# Top_level.net
KiCad netlist of a schematic drawn in Altium Designer
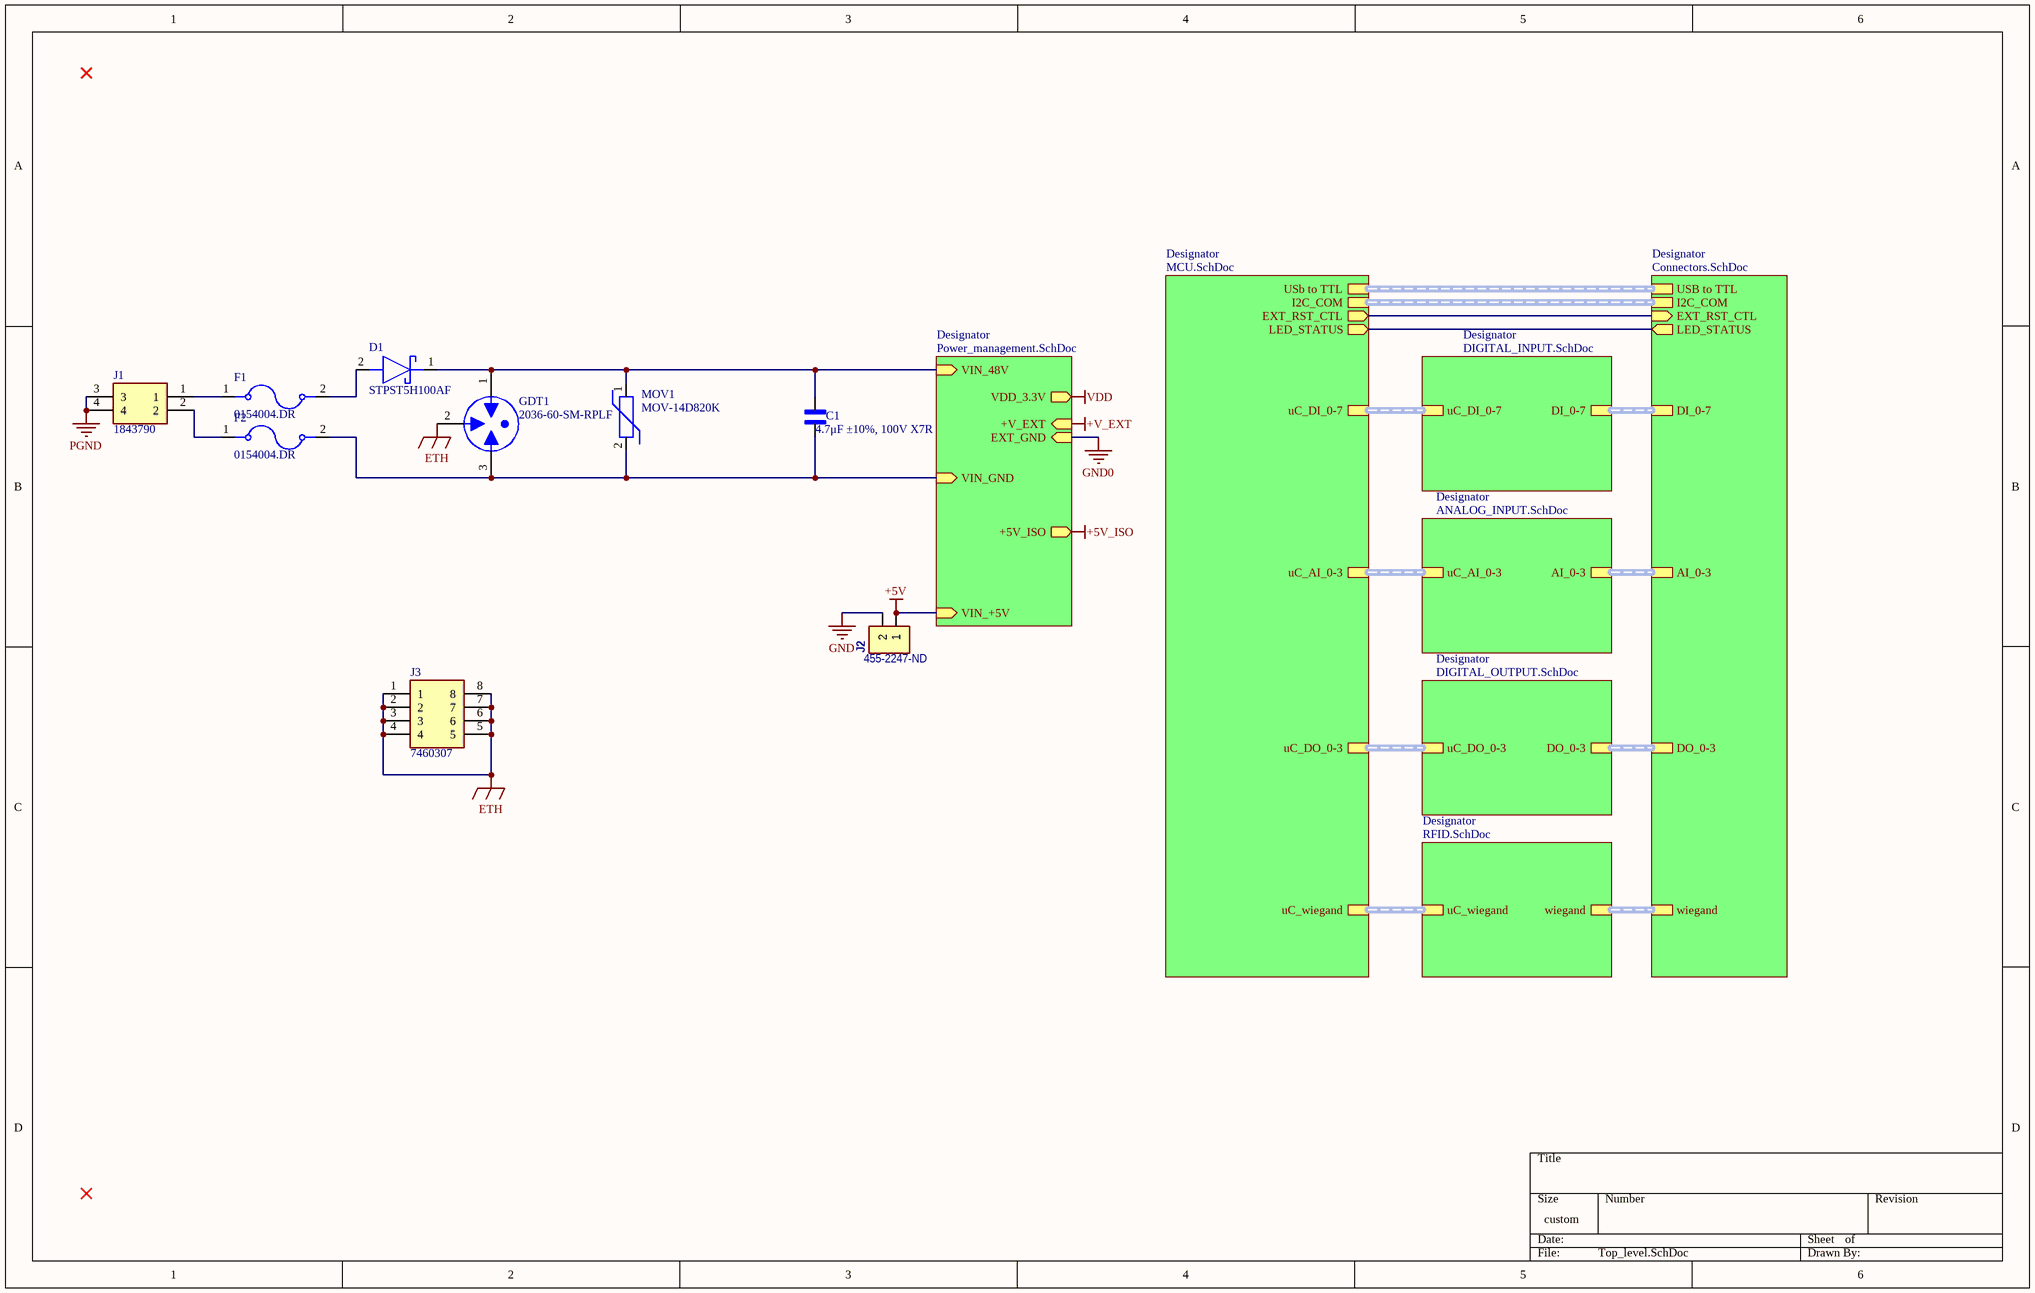
[diagram p0: Top_level.SchDoc]

(export (version "E")
  (design (tool "Eeschema 10.0.6"))
  (components
    (comp (ref "C1")
      (value "4.7μF ±10%, 100V X7R")
      (footprint "1210_C")
      (fields (field (name "MP") "LD03ZD475MAB2A"))
      (libsource (lib "DC_DC") (part "CAP"))
    )
    (comp (ref "D1")
      (value "STPST5H100AF")
      (footprint "SODFL4724X103N")
      (description "Schottky Diode")
      (fields (field (name "MOUSER PART NUMBER") "511-STPST5H100AF"))
      (libsource (lib "DC_DC") (part "STPST5H100AF"))
    )
    (comp (ref "F1")
      (value "0154004.DR")
      (footprint "FUSE_0154004.DR")
      (description "154/154T/154L/154TL Series OMNI-BLOKÂ® Fuse and Holder Assembly")
      (libsource (lib "DC_DC") (part "0154004.DR"))
    )
    (comp (ref "F2")
      (value "0154004.DR")
      (footprint "FUSE_0154004.DR")
      (description "154/154T/154L/154TL Series OMNI-BLOKÂ® Fuse and Holder Assembly")
      (libsource (lib "DC_DC") (part "0154004.DR"))
    )
    (comp (ref "GDT1")
      (value "2036-60-SM-RPLF")
      (footprint "2036-60-SM-RPLF")
      (description "Gas Discharge Tubes - GDTs / Gas Plasma Arrestors Sparkover100V/s 600V Miniature 3 Pole")
      (libsource (lib "DC_DC") (part "2036-60-SM-RPLF"))
    )
    (comp (ref "J1")
      (value "1843790")
      (footprint "SamacSys:1843790")
      (description "Connector")
      (fields (field (name "MOUSER PART NUMBER") "651-1843790"))
      (libsource (lib "*") (part "1843790"))
    )
    (comp (ref "J2")
      (value "455-2247-ND")
      (footprint "CON_HDR1x2")
      (libsource (lib "IIOT_GATEWAY_MT7621") (part "CON_HDR1x2"))
    )
    (comp (ref "J3")
      (value "7460307")
      (footprint "7460307")
      (description "Connector")
      (fields (field (name "MOUSER PART NUMBER") "710-7460307"))
      (libsource (lib "DC_DC") (part "7460307"))
    )
    (comp (ref "MOV1")
      (value "MOV-14D820K")
      (footprint "MOV-14D820K")
      (description "Varistors 82volts 14mm")
      (fields (field (name "MP") "MOV-14D471K") (field (name "MF") "Bourns"))
      (libsource (lib "DC_DC") (part "MOV-14D820K"))
    )
  )
  (nets
    (net (code "1") (name "+5V") (class "Default")
      (node (ref "J2") (pin "1") (pinfunction "1_1") (pintype "passive"))
    )
    (net (code "11") (name "/VIN_48V") (class "Default")
      (node (ref "C1") (pin "1") (pinfunction "1_1") (pintype "passive"))
      (node (ref "D1") (pin "1") (pinfunction "K_1") (pintype "passive"))
      (node (ref "GDT1") (pin "1") (pinfunction "A_1") (pintype "passive"))
      (node (ref "MOV1") (pin "1") (pinfunction "1_1") (pintype "bidirectional"))
    )
    (net (code "12") (name "/VIN_GND") (class "Default")
      (node (ref "C1") (pin "2") (pinfunction "2_2") (pintype "passive"))
      (node (ref "F2") (pin "2") (pinfunction "2_2") (pintype "passive"))
      (node (ref "GDT1") (pin "3") (pinfunction "B_3") (pintype "passive"))
      (node (ref "MOV1") (pin "2") (pinfunction "2_2") (pintype "bidirectional"))
    )
    (net (code "18") (name "ETH") (class "Default")
      (node (ref "GDT1") (pin "2") (pinfunction "E_2") (pintype "passive"))
      (node (ref "J3") (pin "1") (pinfunction "1_1") (pintype "passive"))
      (node (ref "J3") (pin "2") (pinfunction "2_2") (pintype "passive"))
      (node (ref "J3") (pin "3") (pinfunction "3_3") (pintype "passive"))
      (node (ref "J3") (pin "4") (pinfunction "4_4") (pintype "passive"))
      (node (ref "J3") (pin "5") (pinfunction "5_5") (pintype "passive"))
      (node (ref "J3") (pin "6") (pinfunction "6_6") (pintype "passive"))
      (node (ref "J3") (pin "7") (pinfunction "7_7") (pintype "passive"))
      (node (ref "J3") (pin "8") (pinfunction "8_8") (pintype "passive"))
    )
    (net (code "19") (name "GND") (class "Default")
      (node (ref "J2") (pin "2") (pinfunction "2_2") (pintype "passive"))
    )
    (net (code "21") (name "Net-(D1-A)") (class "Default")
      (node (ref "D1") (pin "2") (pinfunction "A_2") (pintype "passive"))
      (node (ref "F1") (pin "2") (pinfunction "2_2") (pintype "passive"))
    )
    (net (code "22") (name "Net-(F1-Pad1)") (class "Default")
      (node (ref "F1") (pin "1") (pinfunction "1_1") (pintype "passive"))
      (node (ref "J1") (pin "1") (pinfunction "1_1") (pintype "passive"))
    )
    (net (code "23") (name "Net-(F2-Pad1)") (class "Default")
      (node (ref "F2") (pin "1") (pinfunction "1_1") (pintype "passive"))
      (node (ref "J1") (pin "2") (pinfunction "2_2") (pintype "passive"))
    )
    (net (code "24") (name "PGND") (class "Default")
      (node (ref "J1") (pin "3") (pinfunction "3_3") (pintype "passive"))
      (node (ref "J1") (pin "4") (pinfunction "4_4") (pintype "passive"))
    )
  )
)
